# Motor_Interface_-_Pre-Charge_Interface.net
KiCad netlist of a schematic drawn in Altium Designer
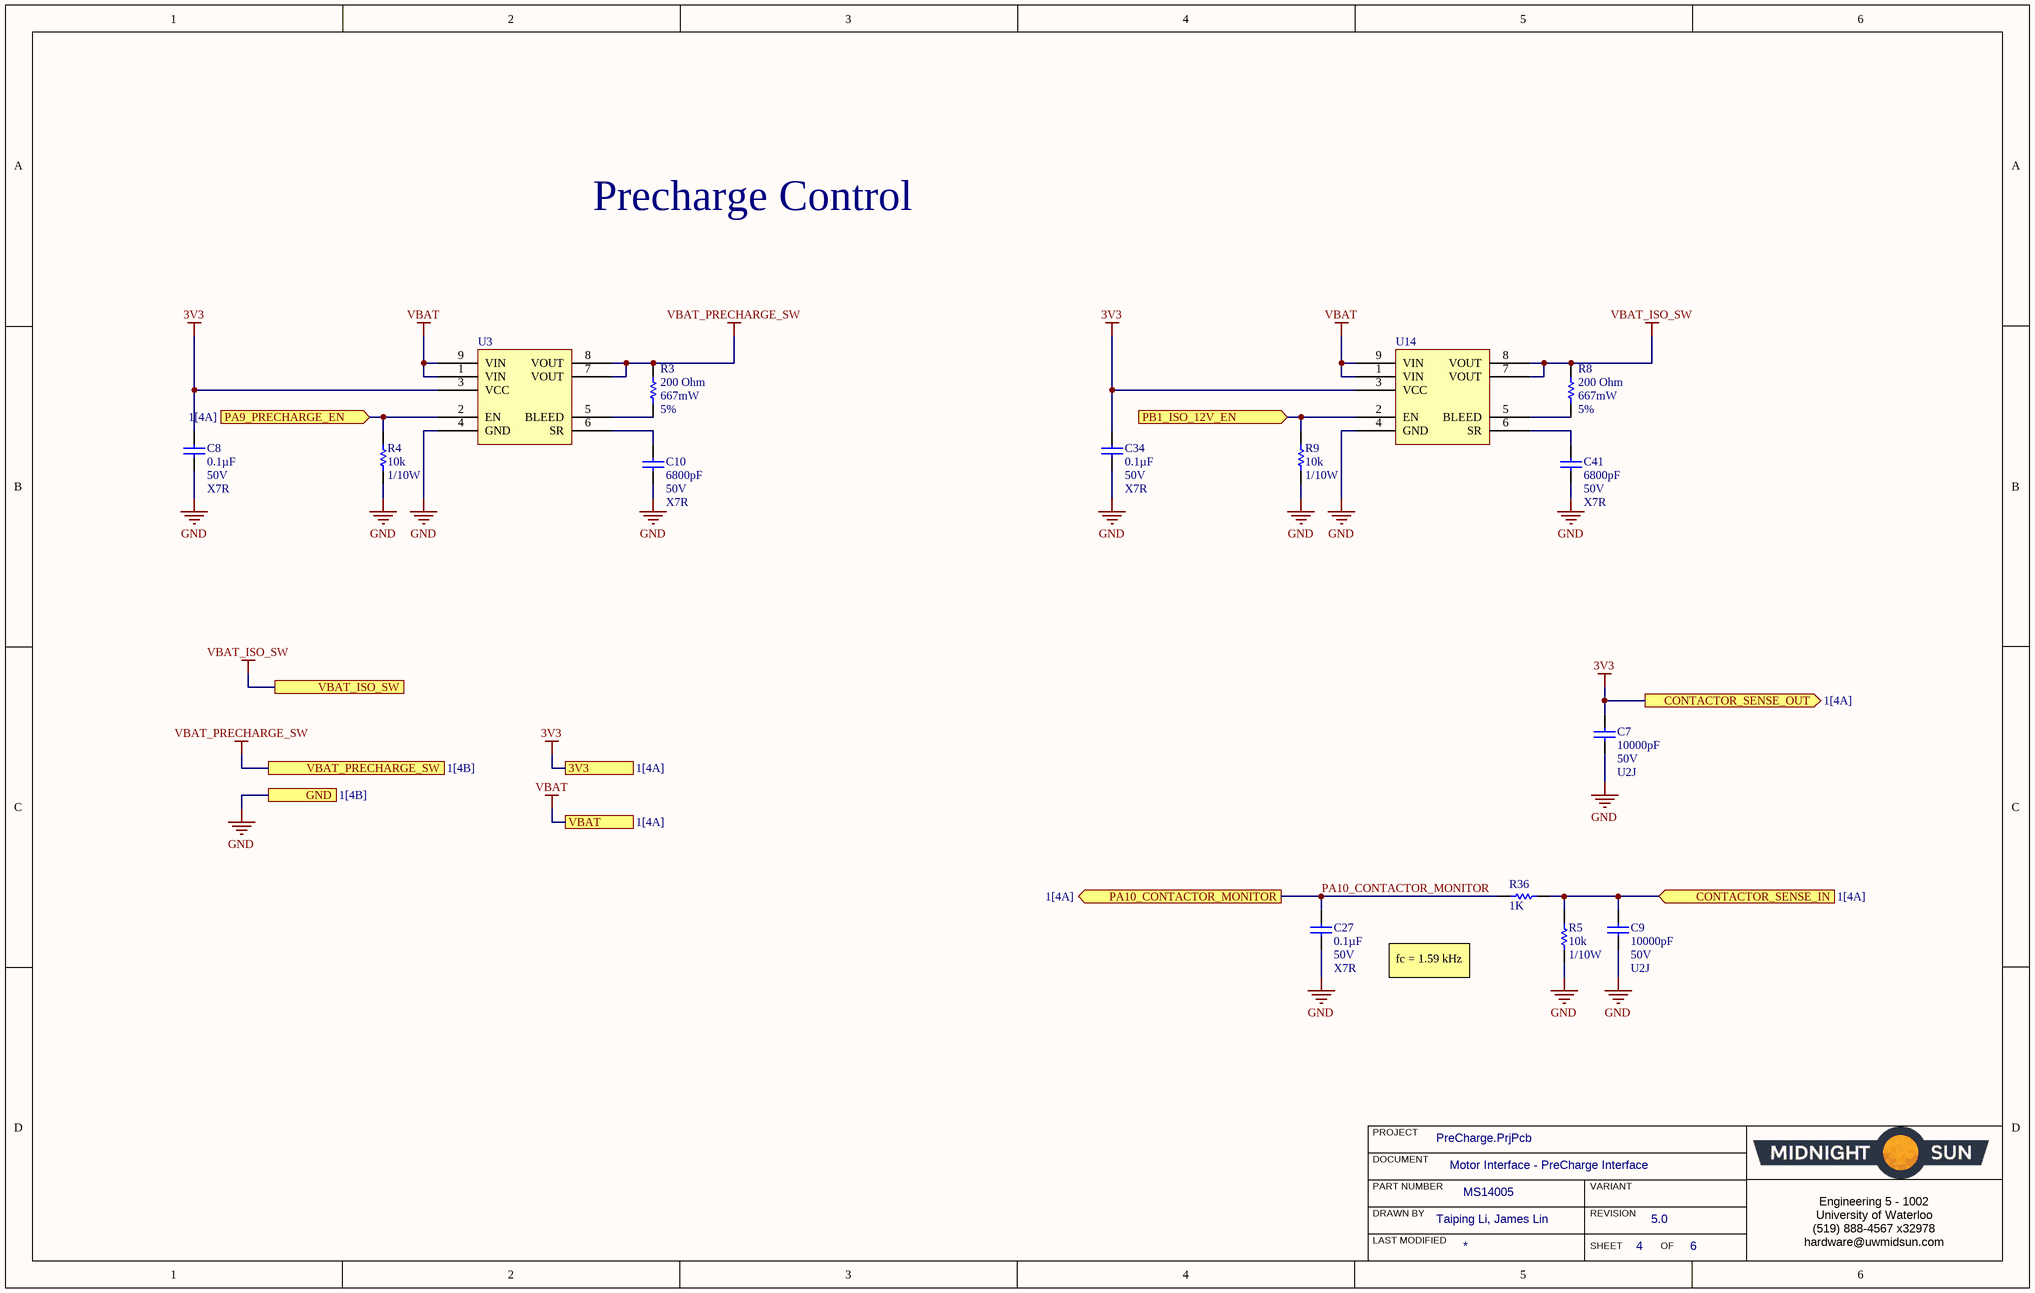
[diagram p0: Motor Interface - Pre-Charge Interface.SchDoc]

(export (version "E")
  (design (tool "Eeschema 10.0.6"))
  (components
    (comp (ref "C7")
      (value "CAP CER 10nF 50V 5% X7R 0603")
      (footprint "CAP, 0603")
      (description "10000pF ±5% 50V Ceramic Capacitor U2J 0603 (1608 Metric)")
      (fields
        (field (name "TOLERANCE") "±5%")
        (field (name "CAPACITANCE") "10000pF")
        (field (name "VOLTAGE") "50V")
        (field (name "TEMPERATURE COEFFICIENT") "U2J")
      )
      (libsource (lib "altium-import") (part "root_0_CAP CER 10nF 50V 5% X7R 0603_"))
    )
    (comp (ref "C8")
      (value "CAP CER 0.1UF 50V 10% X7R 0603")
      (footprint "CAP, 0603")
      (description "0.10µF ±10% 50V Ceramic Capacitor X7R 0603 (1608 Metric)")
      (fields
        (field (name "TOLERANCE") "±10%")
        (field (name "CAPACITANCE") "0.1µF")
        (field (name "VOLTAGE") "50V")
        (field (name "TEMPERATURE COEFFICIENT") "X7R")
      )
      (libsource (lib "Schematic Diagrams") (part "CAP CER 0.1UF 50V 10% X7R 0603"))
    )
    (comp (ref "C9")
      (value "CAP CER 10nF 50V 5% X7R 0603")
      (footprint "CAP, 0603")
      (description "10000pF ±5% 50V Ceramic Capacitor U2J 0603 (1608 Metric)")
      (fields
        (field (name "TOLERANCE") "±5%")
        (field (name "CAPACITANCE") "10000pF")
        (field (name "VOLTAGE") "50V")
        (field (name "TEMPERATURE COEFFICIENT") "U2J")
      )
      (libsource (lib "altium-import") (part "root_0_CAP CER 10nF 50V 5% X7R 0603_"))
    )
    (comp (ref "C10")
      (value "CAP CER 6800pF 50V 10% X7R 0603")
      (footprint "CAP, 0603")
      (description "6800pF ±10% 50V Ceramic Capacitor X7R 0603 (1608 Metric)")
      (fields
        (field (name "TOLERANCE") "±10%")
        (field (name "CAPACITANCE") "6800pF")
        (field (name "VOLTAGE") "50V")
        (field (name "TEMPERATURE COEFFICIENT") "X7R")
      )
      (libsource (lib "altium-import") (part "root_0_CAP CER 6800pF 50V 10% X7R 0603_"))
    )
    (comp (ref "C27")
      (value "CAP CER 0.1UF 50V 10% X7R 0603")
      (footprint "CAP, 0603")
      (description "0.10µF ±10% 50V Ceramic Capacitor X7R 0603 (1608 Metric)")
      (fields
        (field (name "TOLERANCE") "±10%")
        (field (name "CAPACITANCE") "0.1µF")
        (field (name "VOLTAGE") "50V")
        (field (name "TEMPERATURE COEFFICIENT") "X7R")
      )
      (libsource (lib "Schematic Diagrams") (part "CAP CER 0.1UF 50V 10% X7R 0603"))
    )
    (comp (ref "C34")
      (value "CAP CER 0.1UF 50V 10% X7R 0603")
      (footprint "CAP, 0603")
      (description "0.10µF ±10% 50V Ceramic Capacitor X7R 0603 (1608 Metric)")
      (fields
        (field (name "TOLERANCE") "±10%")
        (field (name "CAPACITANCE") "0.1µF")
        (field (name "VOLTAGE") "50V")
        (field (name "TEMPERATURE COEFFICIENT") "X7R")
      )
      (libsource (lib "Schematic Diagrams") (part "CAP CER 0.1UF 50V 10% X7R 0603"))
    )
    (comp (ref "C41")
      (value "CAP CER 6800pF 50V 10% X7R 0603")
      (footprint "CAP, 0603")
      (description "6800pF ±10% 50V Ceramic Capacitor X7R 0603 (1608 Metric)")
      (fields
        (field (name "TOLERANCE") "±10%")
        (field (name "CAPACITANCE") "6800pF")
        (field (name "VOLTAGE") "50V")
        (field (name "TEMPERATURE COEFFICIENT") "X7R")
      )
      (libsource (lib "altium-import") (part "root_0_CAP CER 6800pF 50V 10% X7R 0603_"))
    )
    (comp (ref "R3")
      (value "200 Ohm")
      (footprint "RES 1206")
      (fields
        (field (name "MANUFACTURER") "Panasonic")
        (field (name "MANUFACTURER PART NUMBER") "ERJ-P08J201V")
        (field (name "TOLERANCE") "5%")
        (field (name "MAX POWER DISSIPATION") "667mW")
      )
      (libsource (lib "Schematic Diagrams") (part "RES 200 OHM 5% 2/3W 1206"))
    )
    (comp (ref "R4")
      (value "RES 10K OHM 1% 1/10W 0603")
      (footprint "RES, 0603")
      (description "RES SMD 10K OHM 1% 1/10W 0603")
      (fields
        (field (name "TOLERANCE") "±1%")
        (field (name "RESISTANCE") "10k")
        (field (name "POWER") "1/10W")
      )
      (libsource (lib "Schematic Diagrams") (part "RES 10K OHM 1% 1/10W 0603"))
    )
    (comp (ref "R5")
      (value "RES 10K OHM 1% 1/10W 0603")
      (footprint "RES, 0603")
      (description "RES SMD 10K OHM 1% 1/10W 0603")
      (fields
        (field (name "TOLERANCE") "±1%")
        (field (name "RESISTANCE") "10k")
        (field (name "POWER") "1/10W")
      )
      (libsource (lib "Schematic Diagrams") (part "RES 10K OHM 1% 1/10W 0603"))
    )
    (comp (ref "R8")
      (value "200 Ohm")
      (footprint "RES 1206")
      (fields
        (field (name "MANUFACTURER") "Panasonic")
        (field (name "MANUFACTURER PART NUMBER") "ERJ-P08J201V")
        (field (name "TOLERANCE") "5%")
        (field (name "MAX POWER DISSIPATION") "667mW")
      )
      (libsource (lib "Schematic Diagrams") (part "RES 200 OHM 5% 2/3W 1206"))
    )
    (comp (ref "R9")
      (value "RES 10K OHM 1% 1/10W 0603")
      (footprint "RES, 0603")
      (description "RES SMD 10K OHM 1% 1/10W 0603")
      (fields
        (field (name "TOLERANCE") "±1%")
        (field (name "RESISTANCE") "10k")
        (field (name "POWER") "1/10W")
      )
      (libsource (lib "Schematic Diagrams") (part "RES 10K OHM 1% 1/10W 0603"))
    )
    (comp (ref "R36")
      (value "1K")
      (footprint "RES, 0603")
      (description "1k Ohm ±5% 0.1W, 1/10W Chip Resistor 0603 (1608 Metric)")
      (fields
        (field (name "MANUFACTURER") "Yageo")
        (field (name "MANUFACTURER PART NUMBER") "RC0603JR-071KL")
      )
      (libsource (lib "Schematic Diagrams") (part "RES 1K OHM 5% 1/10W 0603"))
    )
    (comp (ref "U3")
      (value "IC LOAD SWITCH ACT-HI 10.5A 8DFN")
      (footprint "IC LOAD SWITCH ACT-HI 10.5A 8DFN")
      (description "NCP45521IMNTWG-H")
      (fields (field (name "MANUFACTURER") "ON Semiconductor"))
      (libsource (lib "Schematic Diagrams") (part "IC LOAD SWITCH ACT-HI 10.5A 8DFN"))
    )
    (comp (ref "U14")
      (value "IC LOAD SWITCH ACT-HI 10.5A 8DFN")
      (footprint "IC LOAD SWITCH ACT-HI 10.5A 8DFN")
      (description "NCP45521IMNTWG-H")
      (fields (field (name "MANUFACTURER") "ON Semiconductor"))
      (libsource (lib "Schematic Diagrams") (part "IC LOAD SWITCH ACT-HI 10.5A 8DFN"))
    )
  )
  (nets
    (net (code "1") (name "/CONTACTOR_SENSE_IN") (class "Default")
      (node (ref "C9") (pin "1") (pinfunction "1_1") (pintype "passive"))
      (node (ref "R36") (pin "2") (pinfunction "2_2") (pintype "passive"))
      (node (ref "R5") (pin "1") (pinfunction "1_1") (pintype "passive"))
    )
    (net (code "2") (name "/PA9_PRECHARGE_EN") (class "Default")
      (node (ref "R4") (pin "1") (pinfunction "1_1") (pintype "passive"))
      (node (ref "U3") (pin "2") (pinfunction "EN_2") (pintype "passive"))
    )
    (net (code "3") (name "/PA10_CONTACTOR_MONITOR") (class "Default")
      (node (ref "C27") (pin "1") (pinfunction "1_1") (pintype "passive"))
      (node (ref "R36") (pin "1") (pinfunction "1_1") (pintype "passive"))
    )
    (net (code "4") (name "/PB1_ISO_12V_EN") (class "Default")
      (node (ref "R9") (pin "1") (pinfunction "1_1") (pintype "passive"))
      (node (ref "U14") (pin "2") (pinfunction "EN_2") (pintype "passive"))
    )
    (net (code "5") (name "3V3") (class "Default")
      (node (ref "C34") (pin "1") (pinfunction "1_1") (pintype "passive"))
      (node (ref "C7") (pin "1") (pinfunction "1_1") (pintype "passive"))
      (node (ref "C8") (pin "1") (pinfunction "1_1") (pintype "passive"))
      (node (ref "U14") (pin "3") (pinfunction "VCC_3") (pintype "passive"))
      (node (ref "U3") (pin "3") (pinfunction "VCC_3") (pintype "passive"))
    )
    (net (code "6") (name "GND") (class "Default")
      (node (ref "C10") (pin "2") (pinfunction "2_2") (pintype "passive"))
      (node (ref "C27") (pin "2") (pinfunction "2_2") (pintype "passive"))
      (node (ref "C34") (pin "2") (pinfunction "2_2") (pintype "passive"))
      (node (ref "C41") (pin "2") (pinfunction "2_2") (pintype "passive"))
      (node (ref "C7") (pin "2") (pinfunction "2_2") (pintype "passive"))
      (node (ref "C8") (pin "2") (pinfunction "2_2") (pintype "passive"))
      (node (ref "C9") (pin "2") (pinfunction "2_2") (pintype "passive"))
      (node (ref "R4") (pin "2") (pinfunction "2_2") (pintype "passive"))
      (node (ref "R5") (pin "2") (pinfunction "2_2") (pintype "passive"))
      (node (ref "R9") (pin "2") (pinfunction "2_2") (pintype "passive"))
      (node (ref "U14") (pin "4") (pinfunction "GND_4") (pintype "passive"))
      (node (ref "U3") (pin "4") (pinfunction "GND_4") (pintype "passive"))
    )
    (net (code "7") (name "Net-(U3-BLEED)") (class "Default")
      (node (ref "R3") (pin "2") (pinfunction "2_2") (pintype "passive"))
      (node (ref "U3") (pin "5") (pinfunction "BLEED_5") (pintype "passive"))
    )
    (net (code "8") (name "Net-(U3-SR)") (class "Default")
      (node (ref "C10") (pin "1") (pinfunction "1_1") (pintype "passive"))
      (node (ref "U3") (pin "6") (pinfunction "SR_6") (pintype "passive"))
    )
    (net (code "9") (name "Net-(U14-BLEED)") (class "Default")
      (node (ref "R8") (pin "2") (pinfunction "2_2") (pintype "passive"))
      (node (ref "U14") (pin "5") (pinfunction "BLEED_5") (pintype "passive"))
    )
    (net (code "10") (name "Net-(U14-SR)") (class "Default")
      (node (ref "C41") (pin "1") (pinfunction "1_1") (pintype "passive"))
      (node (ref "U14") (pin "6") (pinfunction "SR_6") (pintype "passive"))
    )
    (net (code "11") (name "VBAT") (class "Default")
      (node (ref "U14") (pin "1") (pinfunction "VIN_1") (pintype "passive"))
      (node (ref "U14") (pin "9") (pinfunction "VIN_9") (pintype "passive"))
      (node (ref "U3") (pin "1") (pinfunction "VIN_1") (pintype "passive"))
      (node (ref "U3") (pin "9") (pinfunction "VIN_9") (pintype "passive"))
    )
    (net (code "12") (name "VBAT_ISO_SW") (class "Default")
      (node (ref "R8") (pin "1") (pinfunction "1_1") (pintype "passive"))
      (node (ref "U14") (pin "7") (pinfunction "VOUT_7") (pintype "passive"))
      (node (ref "U14") (pin "8") (pinfunction "VOUT_8") (pintype "passive"))
    )
    (net (code "13") (name "VBAT_PRECHARGE_SW") (class "Default")
      (node (ref "R3") (pin "1") (pinfunction "1_1") (pintype "passive"))
      (node (ref "U3") (pin "7") (pinfunction "VOUT_7") (pintype "passive"))
      (node (ref "U3") (pin "8") (pinfunction "VOUT_8") (pintype "passive"))
    )
  )
)
